# toaster.net
KiCad netlist of a schematic drawn in Altium Designer
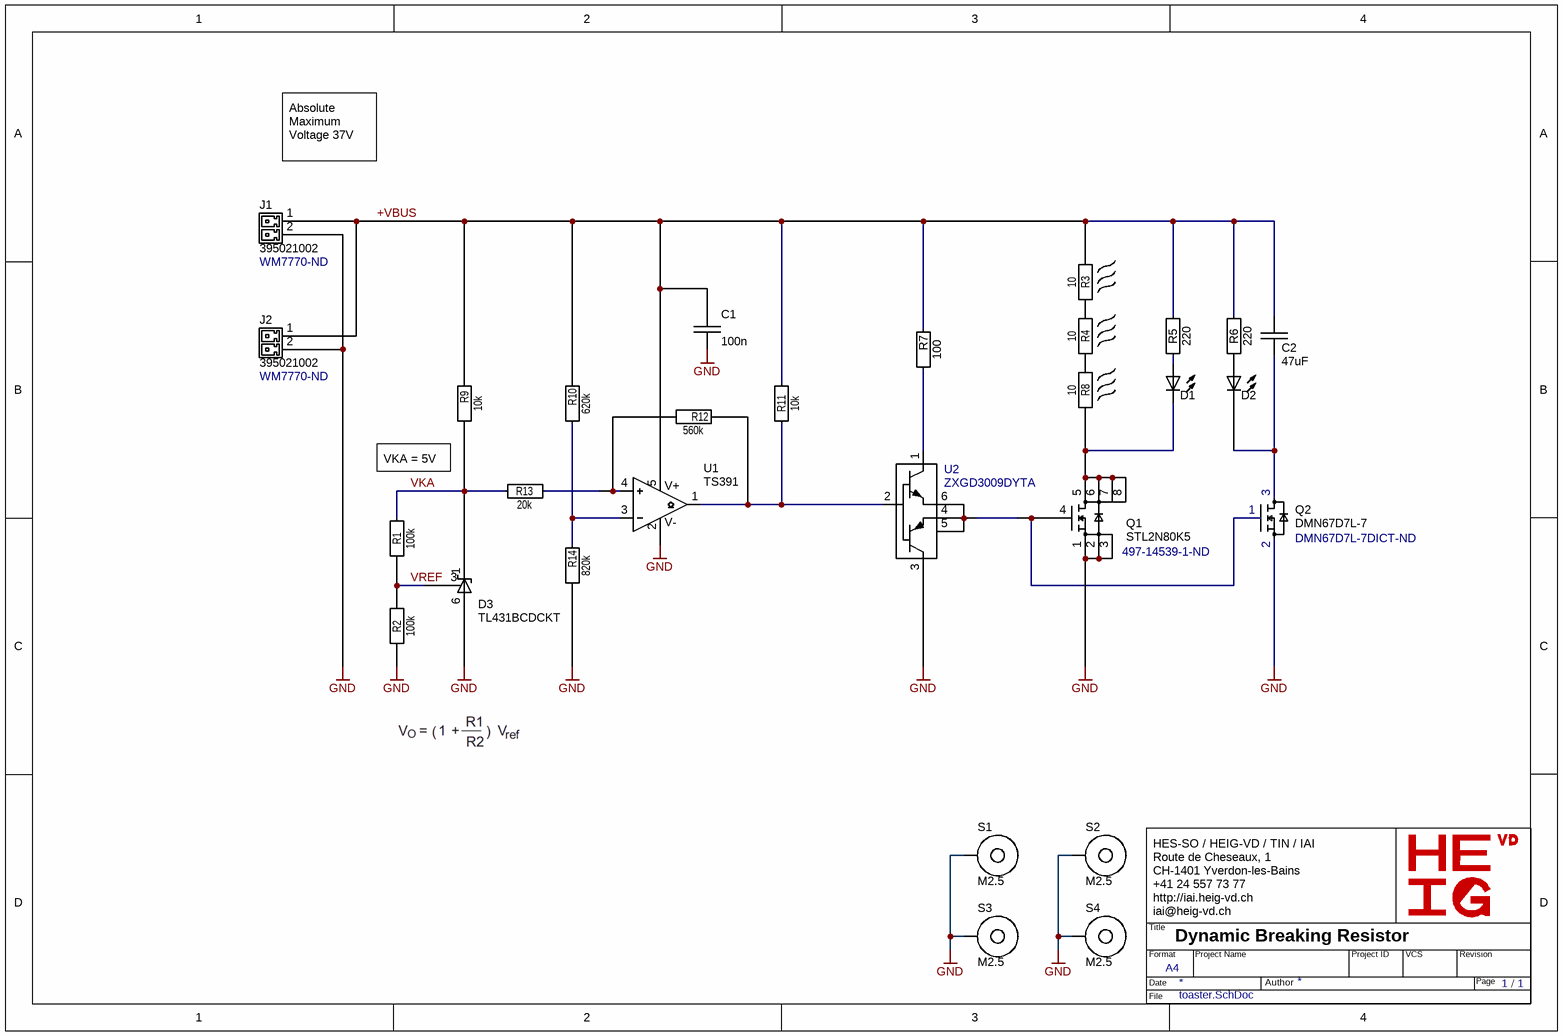
[diagram p0: toaster.SchDoc]

(export (version "E")
  (design (tool "Eeschema 10.0.6"))
  (components
    (comp (ref "C1")
      (value "100n")
      (footprint "SM/C0603")
      (description "Chip Capacitor")
      (fields (field (name "VOLTAGE") "16V"))
      (libsource (lib "toaster") (part "C"))
    )
    (comp (ref "C2")
      (value "47uF")
      (footprint "SM/C0603")
      (description "Chip Capacitor")
      (fields (field (name "VOLTAGE") "16V"))
      (libsource (lib "toaster") (part "C"))
    )
    (comp (ref "D1") (value "~") (footprint "SM/LED0603") (libsource (lib "toaster") (part "LED")))
    (comp (ref "D2") (value "~") (footprint "SM/LED0603") (libsource (lib "toaster") (part "LED")))
    (comp (ref "D3")
      (value "TL431BCDCKT")
      (footprint "SC70-6")
      (description "IC VREF SHUNT ADJ 0.5% SC70-6")
      (libsource (lib "toaster") (part "D ZENER ADJ"))
    )
    (comp (ref "J1")
      (value "395021002")
      (footprint "CONN2/PHOENIX/MC 1.5-2-G-3.5-BLACK")
      (description "TERM BLOCK HDR 2POS 90DEG 3.5MM BLACK")
      (fields (field (name "SUPPLIER PART NUMBER 1") "WM7770-ND"))
      (libsource (lib "toaster") (part "CONN 2 PHOENIX 3.5 mm"))
    )
    (comp (ref "J2")
      (value "395021002")
      (footprint "CONN2/PHOENIX/MC 1.5-2-G-3.5-BLACK")
      (description "TERM BLOCK HDR 2POS 90DEG 3.5MM BLACK")
      (fields (field (name "SUPPLIER PART NUMBER 1") "WM7770-ND"))
      (libsource (lib "toaster") (part "CONN 2 PHOENIX 3.5 mm"))
    )
    (comp (ref "Q1")
      (value "STL2N80K5")
      (footprint "PG-TDSON-8_INF")
      (description "MOSFET N-CH 800V 2A POWERFLATN-Channel 800 V 2A (Tc) 33W (Tc) Surface Mount PowerFlat™ (5x6)")
      (fields (field (name "SUPPLIER PART NUMBER 1") "497-14539-1-ND"))
      (libsource (lib "toaster") (part "BSC0502NSIATMA1"))
    )
    (comp (ref "Q2")
      (value "DMN67D7L-7")
      (footprint "SOT23-3")
      (description "MOSFET N-CH 60V 210MA SOT23-3")
      (fields (field (name "SUPPLIER PART NUMBER 1") "DMN67D7L-7DICT-ND"))
      (libsource (lib "toaster") (part "FDN335"))
    )
    (comp (ref "R1")
      (value "100k")
      (footprint "SM/R0805")
      (description "Chip Resistor SMD")
      (libsource (lib "toaster") (part "R"))
    )
    (comp (ref "R2")
      (value "100k")
      (footprint "SM/R0805")
      (description "Chip Resistor SMD")
      (libsource (lib "toaster") (part "R"))
    )
    (comp (ref "R3")
      (value "10")
      (footprint "RW5S0FA")
      (description "Chip Resistor SMD")
      (libsource (lib "toaster") (part "RT"))
    )
    (comp (ref "R4")
      (value "10")
      (footprint "RW5S0FA")
      (description "Chip Resistor SMD")
      (libsource (lib "toaster") (part "RT"))
    )
    (comp (ref "R5")
      (value "220")
      (footprint "SM/R0603")
      (description "Chip Resistor SMD")
      (libsource (lib "toaster") (part "R"))
    )
    (comp (ref "R6")
      (value "220")
      (footprint "SM/R0603")
      (description "Chip Resistor SMD")
      (libsource (lib "toaster") (part "R"))
    )
    (comp (ref "R7")
      (value "100")
      (footprint "SM/R0603")
      (description "Chip Resistor SMD")
      (libsource (lib "") (part "R_2"))
    )
    (comp (ref "R8")
      (value "10")
      (footprint "RW5S0FA")
      (description "Chip Resistor SMD")
      (libsource (lib "toaster") (part "RT"))
    )
    (comp (ref "R9")
      (value "10k")
      (footprint "SM/R0805")
      (description "Chip Resistor SMD")
      (libsource (lib "toaster") (part "R"))
    )
    (comp (ref "R10")
      (value "620k")
      (footprint "SM/R0805")
      (description "Chip Resistor SMD")
      (libsource (lib "toaster") (part "R"))
    )
    (comp (ref "R11")
      (value "10k")
      (footprint "SM/R0805")
      (description "Chip Resistor SMD")
      (libsource (lib "toaster") (part "R"))
    )
    (comp (ref "R12")
      (value "560k")
      (footprint "SM/R0805")
      (description "Chip Resistor SMD")
      (libsource (lib "") (part "R_1"))
    )
    (comp (ref "R13")
      (value "20k")
      (footprint "SM/R0805")
      (description "Chip Resistor SMD")
      (libsource (lib "") (part "R_1"))
    )
    (comp (ref "R14")
      (value "820k")
      (footprint "SM/R0805")
      (description "Chip Resistor SMD")
      (libsource (lib "toaster") (part "R"))
    )
    (comp (ref "S1")
      (value "M2.5")
      (footprint "HW/HOLE/M2.5/VIA")
      (libsource (lib "toaster") (part "HOLE/M2.5"))
    )
    (comp (ref "S2")
      (value "M2.5")
      (footprint "HW/HOLE/M2.5/VIA")
      (libsource (lib "toaster") (part "HOLE/M2.5"))
    )
    (comp (ref "S3")
      (value "M2.5")
      (footprint "HW/HOLE/M2.5/VIA")
      (libsource (lib "toaster") (part "HOLE/M2.5"))
    )
    (comp (ref "S4")
      (value "M2.5")
      (footprint "HW/HOLE/M2.5/VIA")
      (libsource (lib "toaster") (part "HOLE/M2.5"))
    )
    (comp (ref "U1") (value "TS391") (footprint "SOT23-5") (libsource (lib "toaster") (part "TS391")))
    (comp (ref "U2")
      (value "ZXGD3009DYTA")
      (footprint "SC70-6")
      (description "IC GATE DRVR LOW-SIDE SOT363")
      (libsource (lib "toaster") (part "ZXGD3009DY"))
    )
  )
  (nets
    (net (code "1") (name "/+VBUS") (class "Default")
      (node (ref "C1") (pin "2") (pintype "passive"))
      (node (ref "C2") (pin "2") (pintype "passive"))
      (node (ref "J1") (pin "1") (pinfunction "1_1") (pintype "passive"))
      (node (ref "J2") (pin "1") (pinfunction "1_1") (pintype "passive"))
      (node (ref "R10") (pin "2") (pintype "passive"))
      (node (ref "R11") (pin "2") (pintype "passive"))
      (node (ref "R3") (pin "2") (pintype "passive"))
      (node (ref "R5") (pin "2") (pintype "passive"))
      (node (ref "R6") (pin "2") (pintype "passive"))
      (node (ref "R7") (pin "1") (pintype "passive"))
      (node (ref "R9") (pin "2") (pintype "passive"))
      (node (ref "U1") (pin "5") (pinfunction "V+_5") (pintype "passive"))
    )
    (net (code "2") (name "/VKA") (class "Default")
      (node (ref "D3") (pin "1") (pinfunction "Cathode_1") (pintype "passive"))
      (node (ref "R1") (pin "2") (pintype "passive"))
      (node (ref "R13") (pin "2") (pintype "passive"))
      (node (ref "R9") (pin "1") (pintype "passive"))
    )
    (net (code "3") (name "/VREF") (class "Default")
      (node (ref "D3") (pin "3") (pinfunction "Ref_3") (pintype "passive"))
      (node (ref "R1") (pin "1") (pintype "passive"))
      (node (ref "R2") (pin "2") (pintype "passive"))
    )
    (net (code "4") (name "GND") (class "Default")
      (node (ref "C1") (pin "1") (pintype "passive"))
      (node (ref "D3") (pin "6") (pinfunction "Anode_6") (pintype "passive"))
      (node (ref "J1") (pin "2") (pinfunction "2_2") (pintype "passive"))
      (node (ref "J2") (pin "2") (pinfunction "2_2") (pintype "passive"))
      (node (ref "Q1") (pin "1") (pinfunction "S_1") (pintype "passive"))
      (node (ref "Q1") (pin "2") (pinfunction "S_2") (pintype "passive"))
      (node (ref "Q1") (pin "3") (pinfunction "S_3") (pintype "passive"))
      (node (ref "Q2") (pin "2") (pinfunction "S_2") (pintype "passive"))
      (node (ref "R14") (pin "1") (pintype "passive"))
      (node (ref "R2") (pin "1") (pintype "passive"))
      (node (ref "S1") (pin "1") (pinfunction "1_1") (pintype "passive"))
      (node (ref "S2") (pin "1") (pinfunction "1_1") (pintype "passive"))
      (node (ref "S3") (pin "1") (pinfunction "1_1") (pintype "passive"))
      (node (ref "S4") (pin "1") (pinfunction "1_1") (pintype "passive"))
      (node (ref "U1") (pin "2") (pinfunction "V-_2") (pintype "passive"))
      (node (ref "U2") (pin "3") (pinfunction "VEE_3") (pintype "passive"))
    )
    (net (code "5") (name "Net-(D1-Pad1)") (class "Default")
      (node (ref "D1") (pin "1") (pinfunction "1_1") (pintype "passive"))
      (node (ref "R5") (pin "1") (pintype "passive"))
    )
    (net (code "6") (name "Net-(D1-Pad2)") (class "Default")
      (node (ref "D1") (pin "2") (pinfunction "2_2") (pintype "passive"))
      (node (ref "Q1") (pin "5") (pinfunction "D_5") (pintype "passive"))
      (node (ref "Q1") (pin "6") (pinfunction "D_6") (pintype "passive"))
      (node (ref "Q1") (pin "7") (pinfunction "D_7") (pintype "passive"))
      (node (ref "Q1") (pin "8") (pinfunction "D_8") (pintype "passive"))
      (node (ref "R8") (pin "1") (pintype "passive"))
    )
    (net (code "7") (name "Net-(D2-Pad1)") (class "Default")
      (node (ref "D2") (pin "1") (pinfunction "1_1") (pintype "passive"))
      (node (ref "R6") (pin "1") (pintype "passive"))
    )
    (net (code "8") (name "Net-(Q1-Gate)") (class "Default")
      (node (ref "Q1") (pin "4") (pinfunction "Gate_4") (pintype "passive"))
      (node (ref "Q2") (pin "1") (pinfunction "G_1") (pintype "passive"))
      (node (ref "U2") (pin "4") (pinfunction "SINK_4") (pintype "passive"))
      (node (ref "U2") (pin "5") (pinfunction "SINK_5") (pintype "passive"))
      (node (ref "U2") (pin "6") (pinfunction "SOURCE_6") (pintype "passive"))
    )
    (net (code "9") (name "Net-(Q2-D)") (class "Default")
      (node (ref "C2") (pin "1") (pintype "passive"))
      (node (ref "D2") (pin "2") (pinfunction "2_2") (pintype "passive"))
      (node (ref "Q2") (pin "3") (pinfunction "D_3") (pintype "passive"))
    )
    (net (code "10") (name "Net-(R3-Pad1)") (class "Default")
      (node (ref "R3") (pin "1") (pintype "passive"))
      (node (ref "R4") (pin "2") (pintype "passive"))
    )
    (net (code "11") (name "Net-(R4-Pad1)") (class "Default")
      (node (ref "R4") (pin "1") (pintype "passive"))
      (node (ref "R8") (pin "2") (pintype "passive"))
    )
    (net (code "12") (name "Net-(U1-IN+)") (class "Default")
      (node (ref "R12") (pin "2") (pintype "passive"))
      (node (ref "R13") (pin "1") (pintype "passive"))
      (node (ref "U1") (pin "4") (pinfunction "IN+_4") (pintype "passive"))
    )
    (net (code "13") (name "Net-(U1-IN-)") (class "Default")
      (node (ref "R10") (pin "1") (pintype "passive"))
      (node (ref "R14") (pin "2") (pintype "passive"))
      (node (ref "U1") (pin "3") (pinfunction "IN-_3") (pintype "passive"))
    )
    (net (code "14") (name "Net-(U1-OUT)") (class "Default")
      (node (ref "R11") (pin "1") (pintype "passive"))
      (node (ref "R12") (pin "1") (pintype "passive"))
      (node (ref "U1") (pin "1") (pinfunction "OUT_1") (pintype "passive"))
      (node (ref "U2") (pin "2") (pinfunction "IN_2") (pintype "passive"))
    )
    (net (code "15") (name "Net-(U2-VCC)") (class "Default")
      (node (ref "R7") (pin "2") (pintype "passive"))
      (node (ref "U2") (pin "1") (pinfunction "VCC_1") (pintype "passive"))
    )
  )
)
